# CPU.net
KiCad netlist of a schematic drawn in Altium Designer
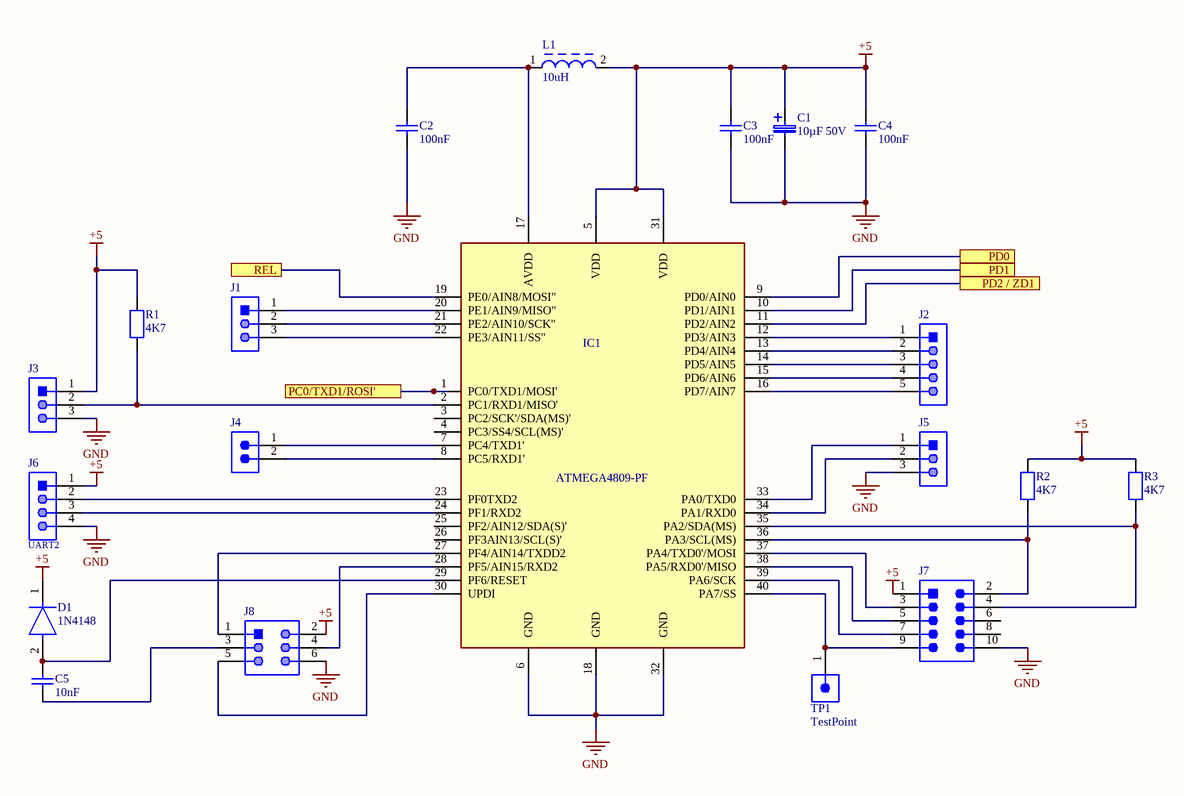
[diagram p0: CPU.SchDoc]

(export (version "E")
  (design (tool "Eeschema 10.0.6"))
  (components
    (comp (ref "C1")
      (value "10µF 50V")
      (footprint "TAP106M050BRW")
      (description "Tantalum Capacitors - Solid Leaded 50V 10uF 20% ESR=1.6 Ohm TAP106M050BRW")
      (fields
        (field (name "MOUSER PART NUMBER") "581-TAP106M050BRW")
        (field (name "MANUFACTURER_PART_NUMBER") "TAP106M050BRW")
      )
      (libsource (lib "SolderStation") (part "capacitor THT radial tantalum"))
    )
    (comp (ref "C2")
      (value "100nF")
      (footprint "CAPC2012X88N")
      (fields (field (name "MANUFACTURER") "Kemet") (field (name "PART NUMBER") "C0402C104K4RACTU"))
      (libsource (lib "SolderStation") (part "Capacitor ceramic 0805"))
    )
    (comp (ref "C3")
      (value "100nF")
      (footprint "CAPC2012X88N")
      (fields (field (name "MANUFACTURER") "Kemet") (field (name "PART NUMBER") "C0402C104K4RACTU"))
      (libsource (lib "SolderStation") (part "Capacitor ceramic 0805"))
    )
    (comp (ref "C4")
      (value "100nF")
      (footprint "CAPC2012X88N")
      (fields (field (name "MANUFACTURER") "Kemet") (field (name "PART NUMBER") "C0402C104K4RACTU"))
      (libsource (lib "SolderStation") (part "Capacitor ceramic 0805"))
    )
    (comp (ref "C5")
      (value "10nF")
      (footprint "CAPC2012X88N")
      (fields (field (name "MANUFACTURER") "Kemet") (field (name "PART NUMBER") "C0402C104K4RACTU"))
      (libsource (lib "SolderStation") (part "Capacitor ceramic 0805"))
    )
    (comp (ref "D1")
      (value "1N4148")
      (footprint "FP-017AG-MFG")
      (description "DIODE GEN PURP 100V 200MA DO35")
      (fields (field (name "VOLTAGE") "100V"))
      (libsource (lib "SolderStation") (part "D 1N4148"))
    )
    (comp (ref "IC1")
      (value "ATMEGA4809-PF")
      (footprint "ATMEGA4809-PF")
      (description "IC MCU 8BIT 48KB FLASH 40DIP")
      (libsource (lib "SolderStation") (part "ATMEGA4809-PF"))
    )
    (comp (ref "J1")
      (value "61300311121")
      (footprint "pin header 1x3")
      (description "THT Vertical Pin Header WR-PHD, Pitch 2.54 mm, Single Row, 3 pins")
      (fields (field (name "MANUFACTURER") "Wurth Elektronik") (field (name "PUBLISHER") "WurthElektronik"))
      (libsource (lib "SolderStation") (part "pin header 1x3pin right connection"))
    )
    (comp (ref "J2")
      (value "61300511121")
      (footprint "pin header 1x5")
      (description "THT Vertical Pin Header WR-PHD, Pitch 2.54 mm, Single Row, 5 pins")
      (fields (field (name "MANUFACTURER") "Wurth Elektronik") (field (name "PUBLISHER") "WurthElektronik"))
      (libsource (lib "SolderStation") (part "pin header 1x5"))
    )
    (comp (ref "J3")
      (value "61300311121")
      (footprint "pin header 1x3")
      (description "THT Vertical Pin Header WR-PHD, Pitch 2.54 mm, Single Row, 3 pins")
      (fields (field (name "MANUFACTURER") "Wurth Elektronik") (field (name "PUBLISHER") "WurthElektronik"))
      (libsource (lib "SolderStation") (part "pin header 1x3pin right connection"))
    )
    (comp (ref "J4")
      (value "61300211121")
      (footprint "61300211121")
      (description "THT Vertical Pin Header WR-PHD, Pitch 2.54 mm, Single Row, 2 pins")
      (libsource (lib "SolderStation") (part "Pin header 1X2 right connection"))
    )
    (comp (ref "J5")
      (value "61300311121")
      (footprint "pin header 1x3")
      (description "THT Vertical Pin Header WR-PHD, Pitch 2.54 mm, Single Row, 3 pins")
      (fields (field (name "MANUFACTURER") "Wurth Elektronik") (field (name "PUBLISHER") "WurthElektronik"))
      (libsource (lib "SolderStation") (part "pin header 1x3pin"))
    )
    (comp (ref "J6")
      (value "UART2")
      (footprint "pin header 1x4")
      (description "THT Vertical Pin Header WR-PHD, Pitch 2.54 mm, Single Row, 4 pins")
      (fields
        (field (name "MANUFACTURER") "Wurth Elektronik")
        (field (name "PART NUMBER") "61300411121")
        (field (name "PUBLISHER") "WurthElektronik")
      )
      (libsource (lib "SolderStation") (part "pin header 1x4 right connection"))
    )
    (comp (ref "J7")
      (value "1-1634688-0")
      (footprint "TECO-1-1634688-0-10_V")
      (fields (field (name "MANUFACTURER") "TE Connectivity"))
      (libsource (lib "SolderStation") (part "CMP-2000-05854-1"))
    )
    (comp (ref "J8")
      (value "61300621121")
      (footprint "pin header 2x6")
      (description "THT Vertical Pin Header WR-PHD, Pitch 2.54 mm, Dual Row, 6 pins")
      (fields (field (name "MANUFACTURER") "Wurth Elektronik") (field (name "PUBLISHER") "WurthElektronik"))
      (libsource (lib "SolderStation") (part "pin header 2x6"))
    )
    (comp (ref "L1")
      (value "10uH")
      (footprint "SMD-1008")
      (description "Power Multilayer Inductor WE-PMI, L = 10.00 µH CMP-0227-00001-1")
      (libsource (lib "SolderStation") (part "Choke SMD 10uH"))
    )
    (comp (ref "R1")
      (value "4K7")
      (footprint "RESC2012X50N")
      (fields (field (name "MANUFACTURER") "Vishay Dale") (field (name "PART NUMBER") "CRCW08050000Z0EA"))
      (libsource (lib "SolderStation") (part "resistor 0805"))
    )
    (comp (ref "R2")
      (value "4K7")
      (footprint "RESC2012X50N")
      (fields (field (name "MANUFACTURER") "Vishay Dale") (field (name "PART NUMBER") "CRCW08050000Z0EA"))
      (libsource (lib "SolderStation") (part "resistor 0805"))
    )
    (comp (ref "R3")
      (value "4K7")
      (footprint "RESC2012X50N")
      (fields (field (name "MANUFACTURER") "Vishay Dale") (field (name "PART NUMBER") "CRCW08050000Z0EA"))
      (libsource (lib "SolderStation") (part "resistor 0805"))
    )
    (comp (ref "TP1")
      (value "TestPoint")
      (footprint "61300111121")
      (libsource (lib "SolderStation") (part "TestPoint"))
    )
  )
  (nets
    (net (code "1") (name "+5") (class "Default")
      (node (ref "C1") (pin "1") (pinfunction "1_1") (pintype "passive"))
      (node (ref "C3") (pin "2") (pinfunction "2_2") (pintype "passive"))
      (node (ref "C4") (pin "2") (pinfunction "2_2") (pintype "passive"))
      (node (ref "D1") (pin "1") (pinfunction "C_1") (pintype "passive"))
      (node (ref "IC1") (pin "31") (pinfunction "VDD_31") (pintype "power_in"))
      (node (ref "IC1") (pin "5") (pinfunction "VDD_5") (pintype "power_in"))
      (node (ref "J3") (pin "1") (pinfunction "1_1") (pintype "passive"))
      (node (ref "J6") (pin "1") (pinfunction "1_1") (pintype "passive"))
      (node (ref "J7") (pin "1") (pinfunction "1_1") (pintype "passive"))
      (node (ref "J8") (pin "2") (pinfunction "2_2") (pintype "passive"))
      (node (ref "L1") (pin "2") (pinfunction "2_2") (pintype "passive"))
      (node (ref "R1") (pin "1") (pinfunction "1_1") (pintype "passive"))
      (node (ref "R2") (pin "2") (pinfunction "2_2") (pintype "passive"))
      (node (ref "R3") (pin "2") (pinfunction "2_2") (pintype "passive"))
    )
    (net (code "2") (name "/PC0{slash}TXD1{slash}ROSI'") (class "Default")
      (node (ref "IC1") (pin "1") (pinfunction "PC0/TXD1/MOSI'_1") (pintype "passive"))
    )
    (net (code "3") (name "/PD0") (class "Default")
      (node (ref "IC1") (pin "9") (pinfunction "PD0/AIN0_9") (pintype "passive"))
    )
    (net (code "4") (name "/PD1") (class "Default")
      (node (ref "IC1") (pin "10") (pinfunction "PD1/AIN1_10") (pintype "passive"))
    )
    (net (code "5") (name "/PD2 {slash} ZD1") (class "Default")
      (node (ref "IC1") (pin "11") (pinfunction "PD2/AIN2_11") (pintype "passive"))
    )
    (net (code "6") (name "/REL") (class "Default")
      (node (ref "IC1") (pin "19") (pinfunction "PE0/AIN8/MOSI\"_19") (pintype "passive"))
    )
    (net (code "7") (name "GND") (class "Default")
      (node (ref "C1") (pin "2") (pinfunction "2_2") (pintype "passive"))
      (node (ref "C2") (pin "1") (pinfunction "1_1") (pintype "passive"))
      (node (ref "C3") (pin "1") (pinfunction "1_1") (pintype "passive"))
      (node (ref "C4") (pin "1") (pinfunction "1_1") (pintype "passive"))
      (node (ref "IC1") (pin "18") (pinfunction "GND_18") (pintype "power_in"))
      (node (ref "IC1") (pin "32") (pinfunction "GND_32") (pintype "power_in"))
      (node (ref "IC1") (pin "6") (pinfunction "GND_6") (pintype "power_in"))
      (node (ref "J3") (pin "3") (pinfunction "3_3") (pintype "passive"))
      (node (ref "J5") (pin "3") (pinfunction "3_3") (pintype "passive"))
      (node (ref "J6") (pin "4") (pinfunction "4_4") (pintype "passive"))
      (node (ref "J7") (pin "10") (pinfunction "10_10") (pintype "passive"))
      (node (ref "J8") (pin "6") (pinfunction "6_6") (pintype "passive"))
    )
    (net (code "8") (name "Net-(C5-Pad1)") (class "Default")
      (node (ref "C5") (pin "1") (pinfunction "1_1") (pintype "passive"))
      (node (ref "J8") (pin "3") (pinfunction "3_3") (pintype "passive"))
    )
    (net (code "9") (name "Net-(D1-A)") (class "Default")
      (node (ref "C5") (pin "2") (pinfunction "2_2") (pintype "passive"))
      (node (ref "D1") (pin "2") (pinfunction "A_2") (pintype "passive"))
      (node (ref "IC1") (pin "29") (pinfunction "PF6/RESET_29") (pintype "passive"))
    )
    (net (code "10") (name "Net-(IC1-AVDD)") (class "Default")
      (node (ref "C2") (pin "2") (pinfunction "2_2") (pintype "passive"))
      (node (ref "IC1") (pin "17") (pinfunction "AVDD_17") (pintype "power_in"))
      (node (ref "L1") (pin "1") (pinfunction "1_1") (pintype "passive"))
    )
    (net (code "11") (name "Net-(IC1-PA0{slash}TXD0)") (class "Default")
      (node (ref "IC1") (pin "33") (pinfunction "PA0/TXD0_33") (pintype "passive"))
      (node (ref "J5") (pin "1") (pinfunction "1_1") (pintype "passive"))
    )
    (net (code "12") (name "Net-(IC1-PA1{slash}RXD0)") (class "Default")
      (node (ref "IC1") (pin "34") (pinfunction "PA1/RXD0_34") (pintype "passive"))
      (node (ref "J5") (pin "2") (pinfunction "2_2") (pintype "passive"))
    )
    (net (code "13") (name "Net-(IC1-PA2{slash}SDA(MS))") (class "Default")
      (node (ref "IC1") (pin "35") (pinfunction "PA2/SDA(MS)_35") (pintype "passive"))
      (node (ref "J7") (pin "4") (pinfunction "4_4") (pintype "passive"))
      (node (ref "R3") (pin "1") (pinfunction "1_1") (pintype "passive"))
    )
    (net (code "14") (name "Net-(IC1-PA3{slash}SCL(MS))") (class "Default")
      (node (ref "IC1") (pin "36") (pinfunction "PA3/SCL(MS)_36") (pintype "passive"))
      (node (ref "J7") (pin "2") (pinfunction "2_2") (pintype "passive"))
      (node (ref "R2") (pin "1") (pinfunction "1_1") (pintype "passive"))
    )
    (net (code "15") (name "Net-(IC1-PA4{slash}TXD0'{slash}MOSI)") (class "Default")
      (node (ref "IC1") (pin "37") (pinfunction "PA4/TXD0'/MOSI_37") (pintype "passive"))
      (node (ref "J7") (pin "3") (pinfunction "3_3") (pintype "passive"))
    )
    (net (code "16") (name "Net-(IC1-PA5{slash}RXD0'{slash}MISO)") (class "Default")
      (node (ref "IC1") (pin "38") (pinfunction "PA5/RXD0'/MISO_38") (pintype "passive"))
      (node (ref "J7") (pin "5") (pinfunction "5_5") (pintype "passive"))
    )
    (net (code "17") (name "Net-(IC1-PA6{slash}SCK)") (class "Default")
      (node (ref "IC1") (pin "39") (pinfunction "PA6/SCK_39") (pintype "passive"))
      (node (ref "J7") (pin "7") (pinfunction "7_7") (pintype "passive"))
    )
    (net (code "18") (name "Net-(IC1-PA7{slash}SS)") (class "Default")
      (node (ref "IC1") (pin "40") (pinfunction "PA7/SS_40") (pintype "passive"))
      (node (ref "J7") (pin "9") (pinfunction "9_9") (pintype "passive"))
      (node (ref "TP1") (pin "1") (pinfunction "1_1") (pintype "passive"))
    )
    (net (code "19") (name "Net-(IC1-PC1{slash}RXD1{slash}MISO')") (class "Default")
      (node (ref "IC1") (pin "2") (pinfunction "PC1/RXD1/MISO'_2") (pintype "passive"))
      (node (ref "J3") (pin "2") (pinfunction "2_2") (pintype "passive"))
      (node (ref "R1") (pin "2") (pinfunction "2_2") (pintype "passive"))
    )
    (net (code "20") (name "Net-(IC1-PC4{slash}TXD1')") (class "Default")
      (node (ref "IC1") (pin "7") (pinfunction "PC4/TXD1'_7") (pintype "passive"))
      (node (ref "J4") (pin "1") (pinfunction "1_1") (pintype "passive"))
    )
    (net (code "21") (name "Net-(IC1-PC5{slash}RXD1')") (class "Default")
      (node (ref "IC1") (pin "8") (pinfunction "PC5/RXD1'_8") (pintype "passive"))
      (node (ref "J4") (pin "2") (pinfunction "2_2") (pintype "passive"))
    )
    (net (code "22") (name "Net-(IC1-PD3{slash}AIN3)") (class "Default")
      (node (ref "IC1") (pin "12") (pinfunction "PD3/AIN3_12") (pintype "passive"))
      (node (ref "J2") (pin "1") (pinfunction "1_1") (pintype "passive"))
    )
    (net (code "23") (name "Net-(IC1-PD4{slash}AIN4)") (class "Default")
      (node (ref "IC1") (pin "13") (pinfunction "PD4/AIN4_13") (pintype "passive"))
      (node (ref "J2") (pin "2") (pinfunction "2_2") (pintype "passive"))
    )
    (net (code "24") (name "Net-(IC1-PD5{slash}AIN5)") (class "Default")
      (node (ref "IC1") (pin "14") (pinfunction "PD5/AIN5_14") (pintype "passive"))
      (node (ref "J2") (pin "3") (pinfunction "3_3") (pintype "passive"))
    )
    (net (code "25") (name "Net-(IC1-PD6{slash}AIN6)") (class "Default")
      (node (ref "IC1") (pin "15") (pinfunction "PD6/AIN6_15") (pintype "passive"))
      (node (ref "J2") (pin "4") (pinfunction "4_4") (pintype "passive"))
    )
    (net (code "26") (name "Net-(IC1-PD7{slash}AIN7)") (class "Default")
      (node (ref "IC1") (pin "16") (pinfunction "PD7/AIN7_16") (pintype "passive"))
      (node (ref "J2") (pin "5") (pinfunction "5_5") (pintype "passive"))
    )
    (net (code "27") (name "Net-(IC1-PE1{slash}AIN9{slash}MISO\")") (class "Default")
      (node (ref "IC1") (pin "20") (pinfunction "PE1/AIN9/MISO\"_20") (pintype "passive"))
      (node (ref "J1") (pin "1") (pinfunction "1_1") (pintype "passive"))
    )
    (net (code "28") (name "Net-(IC1-PE2{slash}AIN10{slash}SCK\")") (class "Default")
      (node (ref "IC1") (pin "21") (pinfunction "PE2/AIN10/SCK\"_21") (pintype "passive"))
      (node (ref "J1") (pin "2") (pinfunction "2_2") (pintype "passive"))
    )
    (net (code "29") (name "Net-(IC1-PE3{slash}AIN11{slash}SS\")") (class "Default")
      (node (ref "IC1") (pin "22") (pinfunction "PE3/AIN11/SS\"_22") (pintype "passive"))
      (node (ref "J1") (pin "3") (pinfunction "3_3") (pintype "passive"))
    )
    (net (code "30") (name "Net-(IC1-PF0TXD2)") (class "Default")
      (node (ref "IC1") (pin "23") (pinfunction "PF0TXD2_23") (pintype "passive"))
      (node (ref "J6") (pin "2") (pinfunction "2_2") (pintype "passive"))
    )
    (net (code "31") (name "Net-(IC1-PF1{slash}RXD2)") (class "Default")
      (node (ref "IC1") (pin "24") (pinfunction "PF1/RXD2_24") (pintype "passive"))
      (node (ref "J6") (pin "3") (pinfunction "3_3") (pintype "passive"))
    )
    (net (code "32") (name "Net-(IC1-PF4{slash}AIN14{slash}TXDD2)") (class "Default")
      (node (ref "IC1") (pin "27") (pinfunction "PF4/AIN14/TXDD2_27") (pintype "passive"))
      (node (ref "J8") (pin "1") (pinfunction "1_1") (pintype "passive"))
    )
    (net (code "33") (name "Net-(IC1-PF5{slash}AIN15{slash}RXD2)") (class "Default")
      (node (ref "IC1") (pin "28") (pinfunction "PF5/AIN15/RXD2_28") (pintype "passive"))
      (node (ref "J8") (pin "4") (pinfunction "4_4") (pintype "passive"))
    )
    (net (code "34") (name "Net-(IC1-UPDI)") (class "Default")
      (node (ref "IC1") (pin "30") (pinfunction "UPDI_30") (pintype "passive"))
      (node (ref "J8") (pin "5") (pinfunction "5_5") (pintype "passive"))
    )
    (net (code "35") (name "unconnected-(IC1-PC2{slash}SCK'{slash}SDA(MS)'-Pad3)") (class "Default")
      (node (ref "IC1") (pin "3") (pinfunction "PC2/SCK'/SDA(MS)'_3") (pintype "passive"))
    )
    (net (code "36") (name "unconnected-(IC1-PC3{slash}SS4{slash}SCL(MS)'-Pad4)") (class "Default")
      (node (ref "IC1") (pin "4") (pinfunction "PC3/SS4/SCL(MS)'_4") (pintype "passive"))
    )
    (net (code "37") (name "unconnected-(IC1-PF2{slash}AIN12{slash}SDA(S)'-Pad25)") (class "Default")
      (node (ref "IC1") (pin "25") (pinfunction "PF2/AIN12/SDA(S)'_25") (pintype "passive"))
    )
    (net (code "38") (name "unconnected-(IC1-PF3AIN13{slash}SCL(S)'-Pad26)") (class "Default")
      (node (ref "IC1") (pin "26") (pinfunction "PF3AIN13/SCL(S)'_26") (pintype "passive"))
    )
    (net (code "39") (name "unconnected-(J7-Pad6)") (class "Default")
      (node (ref "J7") (pin "6") (pinfunction "6_6") (pintype "passive"))
    )
    (net (code "40") (name "unconnected-(J7-Pad8)") (class "Default")
      (node (ref "J7") (pin "8") (pinfunction "8_8") (pintype "passive"))
    )
  )
)
